# LTC6812-1.net
KiCad netlist of a schematic drawn in Altium Designer
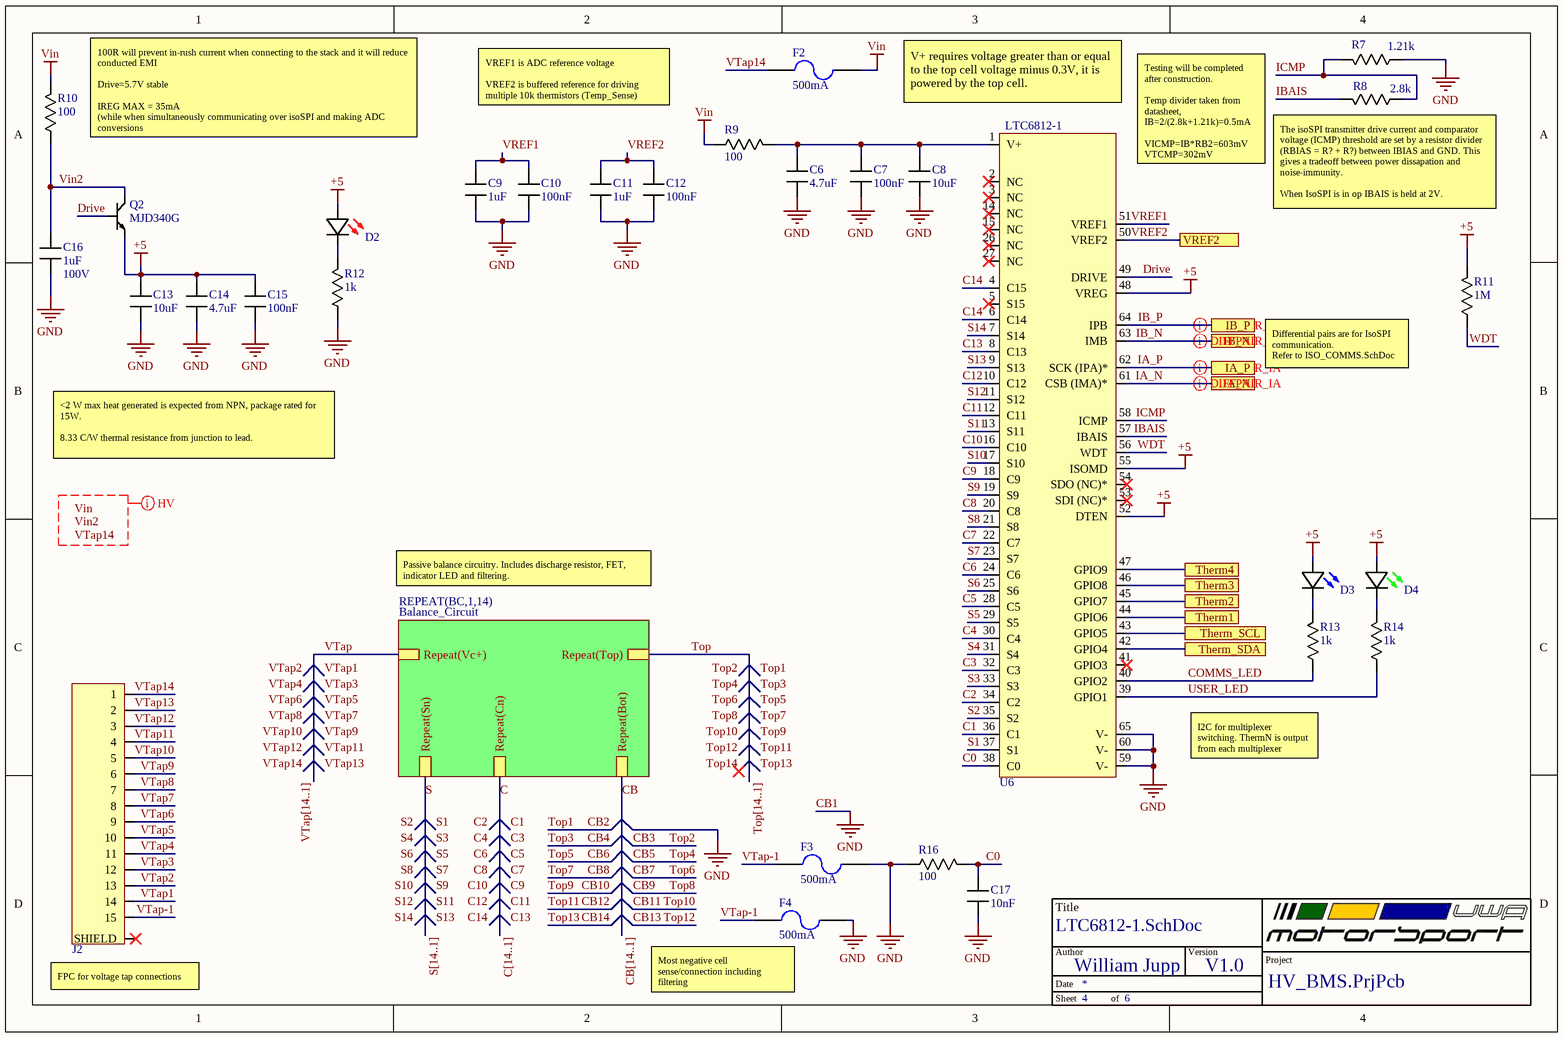
[diagram p0: LTC6812-1.SchDoc]

(export (version "E")
  (design (tool "Eeschema 10.0.6"))
  (components
    (comp (ref "C6")
      (value "4.7uF")
      (footprint "C_0603")
      (description "Capacitor")
      (fields (field (name "Comment") "C"))
      (libsource (lib "Passives") (part "Capacitor"))
    )
    (comp (ref "C7")
      (value "100nF")
      (footprint "C_0603")
      (description "Capacitor")
      (fields (field (name "Comment") "C"))
      (libsource (lib "Passives") (part "Capacitor"))
    )
    (comp (ref "C8")
      (value "10uF")
      (footprint "C_0603")
      (description "Capacitor")
      (fields (field (name "Comment") "C"))
      (libsource (lib "Passives") (part "Capacitor"))
    )
    (comp (ref "C9")
      (value "1uF")
      (footprint "C_0603")
      (description "Bypass caps")
      (fields (field (name "Comment") "C"))
      (libsource (lib "Passives") (part "Capacitor"))
    )
    (comp (ref "C10")
      (value "100nF")
      (footprint "C_0603")
      (description "Bypass caps")
      (fields (field (name "Comment") "C"))
      (libsource (lib "Passives") (part "Capacitor"))
    )
    (comp (ref "C11")
      (value "1uF")
      (footprint "C_0603")
      (description "Bypass caps")
      (fields (field (name "Comment") "C"))
      (libsource (lib "Passives") (part "Capacitor"))
    )
    (comp (ref "C12")
      (value "100nF")
      (footprint "C_0603")
      (description "Bypass caps")
      (fields (field (name "Comment") "C"))
      (libsource (lib "Passives") (part "Capacitor"))
    )
    (comp (ref "C13")
      (value "10uF")
      (footprint "C_0603")
      (description "Capacitor")
      (fields (field (name "Comment") "C"))
      (libsource (lib "Passives") (part "Capacitor"))
    )
    (comp (ref "C14")
      (value "4.7uF")
      (footprint "C_0603")
      (description "Capacitor")
      (fields (field (name "Comment") "C"))
      (libsource (lib "Passives") (part "Capacitor"))
    )
    (comp (ref "C15")
      (value "100nF")
      (footprint "C_0603")
      (description "Capacitor")
      (fields (field (name "Comment") "C"))
      (libsource (lib "Passives") (part "Capacitor"))
    )
    (comp (ref "C16")
      (value "1uF")
      (footprint "C_0603")
      (description "Capacitor")
      (fields (field (name "VOLTAGE") "100V") (field (name "Comment") "C"))
      (libsource (lib "Passives") (part "Capacitor"))
    )
    (comp (ref "C17")
      (value "10nF")
      (footprint "C_0603")
      (description "Capacitor")
      (fields (field (name "Comment") "C"))
      (libsource (lib "Passives") (part "Capacitor"))
    )
    (comp (ref "D2")
      (value "150060SS55040")
      (footprint "LED (0603)")
      (description "LED RED DIFFUSED 0603 SMD")
      (fields (field (name "MANUFACTURER") "Wurth Electronics"))
      (libsource (lib "LEDLib") (part "150060SS55040"))
    )
    (comp (ref "D3")
      (value "150060BS55040")
      (footprint "LED (0603)")
      (description "LED BLUE DIFFUSED 0603 SMD")
      (fields (field (name "MANUFACTURER") "Wurth Electronics"))
      (libsource (lib "LEDLib") (part "150060BS55040"))
    )
    (comp (ref "D4")
      (value "150060GS55040")
      (footprint "LED (0603)")
      (description "LED GREEN DIFFUSED 0603 SMD")
      (fields (field (name "MANUFACTURER") "Wurth Electronics"))
      (libsource (lib "LEDLib") (part "150060GS55040"))
    )
    (comp (ref "F2")
      (value "0466.500NR")
      (footprint "0466.500NR")
      (fields
        (field (name "MANUFACTURER") "Littelfuse")
        (field (name "CURRENT RATING") "500mA")
        (field (name "PUBLISHER") "Altium Limited")
      )
      (libsource (lib "Miscellaneous Devices") (part "Fuse 2"))
    )
    (comp (ref "F3")
      (value "0466.500NR")
      (footprint "0466.500NR")
      (fields
        (field (name "MANUFACTURER") "Littelfuse")
        (field (name "CURRENT RATING") "500mA")
        (field (name "PUBLISHER") "Altium Limited")
      )
      (libsource (lib "Miscellaneous Devices") (part "Fuse 2"))
    )
    (comp (ref "F4")
      (value "0466.500NR")
      (footprint "0466.500NR")
      (fields
        (field (name "MANUFACTURER") "Littelfuse")
        (field (name "CURRENT RATING") "500mA")
        (field (name "PUBLISHER") "Altium Limited")
      )
      (libsource (lib "Miscellaneous Devices") (part "Fuse 2"))
    )
    (comp (ref "J2")
      (value "1-84953-5")
      (footprint "1-84953-5")
      (description "Conn FPC Connector SKT 15 POS 1mm Solder RA SMD T/R")
      (fields (field (name "MANUFACTURER") "TE Connectivity"))
      (libsource (lib "TE_Con") (part "1-84953-5"))
    )
    (comp (ref "Q2")
      (value "MJD340G")
      (footprint "TO-252-3")
      (fields (field (name "MANUFACTURER") "ON Semiconductor"))
      (libsource (lib "NPN") (part "MJD340G"))
    )
    (comp (ref "R7")
      (value "1.21k")
      (footprint "R-0603")
      (description "RB2")
      (fields (field (name "Comment") "Resistor"))
      (libsource (lib "Passives") (part "Resistor"))
    )
    (comp (ref "R8")
      (value "2.8k")
      (footprint "R-0603")
      (description "Resistor")
      (fields (field (name "Comment") "RB1"))
      (libsource (lib "") (part "Resistor_1"))
    )
    (comp (ref "R9")
      (value "100")
      (footprint "R_2010")
      (description "Resistor")
      (fields (field (name "Comment") "ERJ-12ZYJ101U"))
      (libsource (lib "Passives") (part "Resistor"))
    )
    (comp (ref "R10")
      (value "100")
      (footprint "R_2010")
      (description "Resistor")
      (fields (field (name "Comment") "ERJ-12ZYJ101U"))
      (libsource (lib "Passives") (part "Resistor"))
    )
    (comp (ref "R11")
      (value "1M")
      (footprint "R-0603")
      (description "Resistor")
      (libsource (lib "Passives") (part "Resistor"))
    )
    (comp (ref "R12")
      (value "1k")
      (footprint "R-0603")
      (description "Resistor")
      (libsource (lib "Passives") (part "Resistor"))
    )
    (comp (ref "R13")
      (value "1k")
      (footprint "R-0603")
      (description "Resistor")
      (libsource (lib "Passives") (part "Resistor"))
    )
    (comp (ref "R14")
      (value "1k")
      (footprint "R-0603")
      (description "Resistor")
      (libsource (lib "Passives") (part "Resistor"))
    )
    (comp (ref "R16")
      (value "100")
      (footprint "R-0603")
      (description "Resistor")
      (libsource (lib "Passives") (part "Resistor"))
    )
    (comp (ref "U6")
      (value "LTC6812-1")
      (footprint "64-eLQFP")
      (description "Multicell battery stack monitor that measures up to 15 series connected battery cells")
      (libsource (lib "HV_BMS_SCH_LIB") (part "LTC6812-1"))
    )
  )
  (nets
    (net (code "1") (name "+5") (class "Default")
      (node (ref "C13") (pin "2") (pinfunction "2_2") (pintype "passive"))
      (node (ref "C14") (pin "2") (pinfunction "2_2") (pintype "passive"))
      (node (ref "C15") (pin "2") (pinfunction "2_2") (pintype "passive"))
      (node (ref "D2") (pin "2") (pinfunction "A_2") (pintype "passive"))
      (node (ref "D3") (pin "2") (pinfunction "A_2") (pintype "passive"))
      (node (ref "D4") (pin "2") (pinfunction "A_2") (pintype "passive"))
      (node (ref "Q2") (pin "3") (pinfunction "Emitter_3") (pintype "passive"))
      (node (ref "R11") (pin "1") (pinfunction "1_1") (pintype "passive"))
      (node (ref "U6") (pin "48") (pinfunction "VREG_48") (pintype "passive"))
      (node (ref "U6") (pin "52") (pinfunction "DTEN_52") (pintype "passive"))
      (node (ref "U6") (pin "55") (pinfunction "ISOMD_55") (pintype "passive"))
    )
    (net (code "3") (name "/C0") (class "Default")
      (node (ref "C17") (pin "2") (pinfunction "2_2") (pintype "passive"))
      (node (ref "R16") (pin "2") (pinfunction "2_2") (pintype "passive"))
      (node (ref "U6") (pin "38") (pinfunction "C0_38") (pintype "passive"))
    )
    (net (code "4") (name "/C1") (class "Default")
      (node (ref "U6") (pin "36") (pinfunction "C1_36") (pintype "passive"))
    )
    (net (code "5") (name "/C2") (class "Default")
      (node (ref "U6") (pin "34") (pinfunction "C2_34") (pintype "passive"))
    )
    (net (code "6") (name "/C3") (class "Default")
      (node (ref "U6") (pin "32") (pinfunction "C3_32") (pintype "passive"))
    )
    (net (code "7") (name "/C4") (class "Default")
      (node (ref "U6") (pin "30") (pinfunction "C4_30") (pintype "passive"))
    )
    (net (code "8") (name "/C5") (class "Default")
      (node (ref "U6") (pin "28") (pinfunction "C5_28") (pintype "passive"))
    )
    (net (code "9") (name "/C6") (class "Default")
      (node (ref "U6") (pin "24") (pinfunction "C6_24") (pintype "passive"))
    )
    (net (code "10") (name "/C7") (class "Default")
      (node (ref "U6") (pin "22") (pinfunction "C7_22") (pintype "passive"))
    )
    (net (code "11") (name "/C8") (class "Default")
      (node (ref "U6") (pin "20") (pinfunction "C8_20") (pintype "passive"))
    )
    (net (code "12") (name "/C9") (class "Default")
      (node (ref "U6") (pin "18") (pinfunction "C9_18") (pintype "passive"))
    )
    (net (code "13") (name "/C10") (class "Default")
      (node (ref "U6") (pin "16") (pinfunction "C10_16") (pintype "passive"))
    )
    (net (code "14") (name "/C11") (class "Default")
      (node (ref "U6") (pin "12") (pinfunction "C11_12") (pintype "passive"))
    )
    (net (code "15") (name "/C12") (class "Default")
      (node (ref "U6") (pin "10") (pinfunction "C12_10") (pintype "passive"))
    )
    (net (code "16") (name "/C13") (class "Default")
      (node (ref "U6") (pin "8") (pinfunction "C13_8") (pintype "passive"))
    )
    (net (code "17") (name "/C14") (class "Default")
      (node (ref "U6") (pin "4") (pinfunction "C15_4") (pintype "passive"))
      (node (ref "U6") (pin "6") (pinfunction "C14_6") (pintype "passive"))
    )
    (net (code "20") (name "/COMMS_LED") (class "Default")
      (node (ref "R13") (pin "1") (pinfunction "1_1") (pintype "passive"))
      (node (ref "U6") (pin "40") (pinfunction "GPIO2_40") (pintype "passive"))
    )
    (net (code "22") (name "/Drive") (class "Default")
      (node (ref "Q2") (pin "1") (pinfunction "Base_1") (pintype "passive"))
      (node (ref "U6") (pin "49") (pinfunction "DRIVE_49") (pintype "passive"))
    )
    (net (code "23") (name "/IA_N") (class "Default")
      (node (ref "U6") (pin "61") (pinfunction "CSB_(IMA)*_61") (pintype "passive"))
    )
    (net (code "24") (name "/IA_P") (class "Default")
      (node (ref "U6") (pin "62") (pinfunction "SCK_(IPA)*_62") (pintype "passive"))
    )
    (net (code "25") (name "/IBAIS") (class "Default")
      (node (ref "R8") (pin "2") (pinfunction "2_2") (pintype "passive"))
      (node (ref "U6") (pin "57") (pinfunction "IBAIS_57") (pintype "passive"))
    )
    (net (code "26") (name "/IB_N") (class "Default")
      (node (ref "U6") (pin "63") (pinfunction "IMB_63") (pintype "passive"))
    )
    (net (code "27") (name "/IB_P") (class "Default")
      (node (ref "U6") (pin "64") (pinfunction "IPB_64") (pintype "passive"))
    )
    (net (code "28") (name "/ICMP") (class "Default")
      (node (ref "R7") (pin "2") (pinfunction "2_2") (pintype "passive"))
      (node (ref "R8") (pin "1") (pinfunction "1_1") (pintype "passive"))
      (node (ref "U6") (pin "58") (pinfunction "ICMP_58") (pintype "passive"))
    )
    (net (code "30") (name "/S1") (class "Default")
      (node (ref "U6") (pin "37") (pinfunction "S1_37") (pintype "passive"))
    )
    (net (code "31") (name "/S2") (class "Default")
      (node (ref "U6") (pin "35") (pinfunction "S2_35") (pintype "passive"))
    )
    (net (code "32") (name "/S3") (class "Default")
      (node (ref "U6") (pin "33") (pinfunction "S3_33") (pintype "passive"))
    )
    (net (code "33") (name "/S4") (class "Default")
      (node (ref "U6") (pin "31") (pinfunction "S4_31") (pintype "passive"))
    )
    (net (code "34") (name "/S5") (class "Default")
      (node (ref "U6") (pin "29") (pinfunction "S5_29") (pintype "passive"))
    )
    (net (code "35") (name "/S6") (class "Default")
      (node (ref "U6") (pin "25") (pinfunction "S6_25") (pintype "passive"))
    )
    (net (code "36") (name "/S7") (class "Default")
      (node (ref "U6") (pin "23") (pinfunction "S7_23") (pintype "passive"))
    )
    (net (code "37") (name "/S8") (class "Default")
      (node (ref "U6") (pin "21") (pinfunction "S8_21") (pintype "passive"))
    )
    (net (code "38") (name "/S9") (class "Default")
      (node (ref "U6") (pin "19") (pinfunction "S9_19") (pintype "passive"))
    )
    (net (code "39") (name "/S10") (class "Default")
      (node (ref "U6") (pin "17") (pinfunction "S10_17") (pintype "passive"))
    )
    (net (code "40") (name "/S11") (class "Default")
      (node (ref "U6") (pin "13") (pinfunction "S11_13") (pintype "passive"))
    )
    (net (code "41") (name "/S12") (class "Default")
      (node (ref "U6") (pin "11") (pinfunction "S12_11") (pintype "passive"))
    )
    (net (code "42") (name "/S13") (class "Default")
      (node (ref "U6") (pin "9") (pinfunction "S13_9") (pintype "passive"))
    )
    (net (code "43") (name "/S14") (class "Default")
      (node (ref "U6") (pin "7") (pinfunction "S14_7") (pintype "passive"))
    )
    (net (code "45") (name "/Therm1") (class "Default")
      (node (ref "U6") (pin "44") (pinfunction "GPIO6_44") (pintype "passive"))
    )
    (net (code "46") (name "/Therm2") (class "Default")
      (node (ref "U6") (pin "45") (pinfunction "GPIO7_45") (pintype "passive"))
    )
    (net (code "47") (name "/Therm3") (class "Default")
      (node (ref "U6") (pin "46") (pinfunction "GPIO8_46") (pintype "passive"))
    )
    (net (code "48") (name "/Therm4") (class "Default")
      (node (ref "U6") (pin "47") (pinfunction "GPIO9_47") (pintype "passive"))
    )
    (net (code "49") (name "/Therm_SCL") (class "Default")
      (node (ref "U6") (pin "43") (pinfunction "GPIO5_43") (pintype "passive"))
    )
    (net (code "50") (name "/Therm_SDA") (class "Default")
      (node (ref "U6") (pin "42") (pinfunction "GPIO4_42") (pintype "passive"))
    )
    (net (code "67") (name "/USER_LED") (class "Default")
      (node (ref "R14") (pin "1") (pinfunction "1_1") (pintype "passive"))
      (node (ref "U6") (pin "39") (pinfunction "GPIO1_39") (pintype "passive"))
    )
    (net (code "68") (name "/VREF1") (class "Default")
      (node (ref "C10") (pin "2") (pinfunction "2_2") (pintype "passive"))
      (node (ref "C9") (pin "2") (pinfunction "2_2") (pintype "passive"))
      (node (ref "U6") (pin "51") (pinfunction "VREF1_51") (pintype "passive"))
    )
    (net (code "69") (name "/VREF2") (class "Default")
      (node (ref "C11") (pin "2") (pinfunction "2_2") (pintype "passive"))
      (node (ref "C12") (pin "2") (pinfunction "2_2") (pintype "passive"))
      (node (ref "U6") (pin "50") (pinfunction "VREF2_50") (pintype "passive"))
    )
    (net (code "71") (name "/VTap-1") (class "Default")
      (node (ref "F3") (pin "1") (pinfunction "1_1") (pintype "passive"))
      (node (ref "F4") (pin "1") (pinfunction "1_1") (pintype "passive"))
      (node (ref "J2") (pin "15") (pinfunction "15_15") (pintype "passive"))
    )
    (net (code "72") (name "/VTap1") (class "Default")
      (node (ref "J2") (pin "14") (pinfunction "14_14") (pintype "passive"))
    )
    (net (code "73") (name "/VTap2") (class "Default")
      (node (ref "J2") (pin "13") (pinfunction "13_13") (pintype "passive"))
    )
    (net (code "74") (name "/VTap3") (class "Default")
      (node (ref "J2") (pin "12") (pinfunction "12_12") (pintype "passive"))
    )
    (net (code "75") (name "/VTap4") (class "Default")
      (node (ref "J2") (pin "11") (pinfunction "11_11") (pintype "passive"))
    )
    (net (code "76") (name "/VTap5") (class "Default")
      (node (ref "J2") (pin "10") (pinfunction "10_10") (pintype "passive"))
    )
    (net (code "77") (name "/VTap6") (class "Default")
      (node (ref "J2") (pin "9") (pinfunction "9_9") (pintype "passive"))
    )
    (net (code "78") (name "/VTap7") (class "Default")
      (node (ref "J2") (pin "8") (pinfunction "8_8") (pintype "passive"))
    )
    (net (code "79") (name "/VTap8") (class "Default")
      (node (ref "J2") (pin "7") (pinfunction "7_7") (pintype "passive"))
    )
    (net (code "80") (name "/VTap9") (class "Default")
      (node (ref "J2") (pin "6") (pinfunction "6_6") (pintype "passive"))
    )
    (net (code "81") (name "/VTap10") (class "Default")
      (node (ref "J2") (pin "5") (pinfunction "5_5") (pintype "passive"))
    )
    (net (code "82") (name "/VTap11") (class "Default")
      (node (ref "J2") (pin "4") (pinfunction "4_4") (pintype "passive"))
    )
    (net (code "83") (name "/VTap12") (class "Default")
      (node (ref "J2") (pin "3") (pinfunction "3_3") (pintype "passive"))
    )
    (net (code "84") (name "/VTap13") (class "Default")
      (node (ref "J2") (pin "2") (pinfunction "2_2") (pintype "passive"))
    )
    (net (code "85") (name "/VTap14") (class "Default")
      (node (ref "F2") (pin "1") (pinfunction "1_1") (pintype "passive"))
      (node (ref "J2") (pin "1") (pinfunction "1_1") (pintype "passive"))
    )
    (net (code "87") (name "/Vin2") (class "Default")
      (node (ref "C16") (pin "2") (pinfunction "2_2") (pintype "passive"))
      (node (ref "Q2") (pin "2") (pinfunction "Collector_2") (pintype "passive"))
      (node (ref "R10") (pin "1") (pinfunction "1_1") (pintype "passive"))
    )
    (net (code "88") (name "/WDT") (class "Default")
      (node (ref "R11") (pin "2") (pinfunction "2_2") (pintype "passive"))
      (node (ref "U6") (pin "56") (pinfunction "WDT_56") (pintype "passive"))
    )
    (net (code "89") (name "GND") (class "Default")
      (node (ref "C10") (pin "1") (pinfunction "1_1") (pintype "passive"))
      (node (ref "C11") (pin "1") (pinfunction "1_1") (pintype "passive"))
      (node (ref "C12") (pin "1") (pinfunction "1_1") (pintype "passive"))
      (node (ref "C13") (pin "1") (pinfunction "1_1") (pintype "passive"))
      (node (ref "C14") (pin "1") (pinfunction "1_1") (pintype "passive"))
      (node (ref "C15") (pin "1") (pinfunction "1_1") (pintype "passive"))
      (node (ref "C16") (pin "1") (pinfunction "1_1") (pintype "passive"))
      (node (ref "C17") (pin "1") (pinfunction "1_1") (pintype "passive"))
      (node (ref "C6") (pin "1") (pinfunction "1_1") (pintype "passive"))
      (node (ref "C7") (pin "1") (pinfunction "1_1") (pintype "passive"))
      (node (ref "C8") (pin "1") (pinfunction "1_1") (pintype "passive"))
      (node (ref "C9") (pin "1") (pinfunction "1_1") (pintype "passive"))
      (node (ref "F3") (pin "2") (pinfunction "2_2") (pintype "passive"))
      (node (ref "F4") (pin "2") (pinfunction "2_2") (pintype "passive"))
      (node (ref "R12") (pin "1") (pinfunction "1_1") (pintype "passive"))
      (node (ref "R16") (pin "1") (pinfunction "1_1") (pintype "passive"))
      (node (ref "R7") (pin "1") (pinfunction "1_1") (pintype "passive"))
      (node (ref "U6") (pin "59") (pinfunction "V-_59") (pintype "passive"))
      (node (ref "U6") (pin "60") (pinfunction "V-_60") (pintype "passive"))
      (node (ref "U6") (pin "65") (pinfunction "V-_65") (pintype "passive"))
    )
    (net (code "90") (name "Net-(D2-K)") (class "Default")
      (node (ref "D2") (pin "1") (pinfunction "K_1") (pintype "passive"))
      (node (ref "R12") (pin "2") (pinfunction "2_2") (pintype "passive"))
    )
    (net (code "91") (name "Net-(D3-K)") (class "Default")
      (node (ref "D3") (pin "1") (pinfunction "K_1") (pintype "passive"))
      (node (ref "R13") (pin "2") (pinfunction "2_2") (pintype "passive"))
    )
    (net (code "92") (name "Net-(D4-K)") (class "Default")
      (node (ref "D4") (pin "1") (pinfunction "K_1") (pintype "passive"))
      (node (ref "R14") (pin "2") (pinfunction "2_2") (pintype "passive"))
    )
    (net (code "93") (name "Net-(U6-V+)") (class "Default")
      (node (ref "C6") (pin "2") (pinfunction "2_2") (pintype "passive"))
      (node (ref "C7") (pin "2") (pinfunction "2_2") (pintype "passive"))
      (node (ref "C8") (pin "2") (pinfunction "2_2") (pintype "passive"))
      (node (ref "R9") (pin "2") (pinfunction "2_2") (pintype "passive"))
      (node (ref "U6") (pin "1") (pinfunction "V+_1") (pintype "passive"))
    )
    (net (code "94") (name "Vin") (class "Default")
      (node (ref "F2") (pin "2") (pinfunction "2_2") (pintype "passive"))
      (node (ref "R10") (pin "2") (pinfunction "2_2") (pintype "passive"))
      (node (ref "R9") (pin "1") (pinfunction "1_1") (pintype "passive"))
    )
    (net (code "95") (name "unconnected-(J2-SHIELD-PadS)") (class "Default")
      (node (ref "J2") (pin "S") (pinfunction "SHIELD_S") (pintype "passive+no_connect"))
    )
    (net (code "96") (name "unconnected-(U6-GPIO3-Pad41)") (class "Default")
      (node (ref "U6") (pin "41") (pinfunction "GPIO3_41") (pintype "passive+no_connect"))
    )
    (net (code "97") (name "unconnected-(U6-NC-Pad2)") (class "Default")
      (node (ref "U6") (pin "2") (pinfunction "NC_2") (pintype "passive+no_connect"))
    )
    (net (code "98") (name "unconnected-(U6-NC-Pad3)") (class "Default")
      (node (ref "U6") (pin "3") (pinfunction "NC_3") (pintype "passive+no_connect"))
    )
    (net (code "99") (name "unconnected-(U6-NC-Pad14)") (class "Default")
      (node (ref "U6") (pin "14") (pinfunction "NC_14") (pintype "passive+no_connect"))
    )
    (net (code "100") (name "unconnected-(U6-NC-Pad15)") (class "Default")
      (node (ref "U6") (pin "15") (pinfunction "NC_15") (pintype "passive+no_connect"))
    )
    (net (code "101") (name "unconnected-(U6-NC-Pad26)") (class "Default")
      (node (ref "U6") (pin "26") (pinfunction "NC_26") (pintype "passive+no_connect"))
    )
    (net (code "102") (name "unconnected-(U6-NC-Pad27)") (class "Default")
      (node (ref "U6") (pin "27") (pinfunction "NC_27") (pintype "passive+no_connect"))
    )
    (net (code "103") (name "unconnected-(U6-S15-Pad5)") (class "Default")
      (node (ref "U6") (pin "5") (pinfunction "S15_5") (pintype "passive+no_connect"))
    )
    (net (code "104") (name "unconnected-(U6-SDI_(NC)*-Pad53)") (class "Default")
      (node (ref "U6") (pin "53") (pinfunction "SDI_(NC)*_53") (pintype "passive+no_connect"))
    )
    (net (code "105") (name "unconnected-(U6-SDO_(NC)*-Pad54)") (class "Default")
      (node (ref "U6") (pin "54") (pinfunction "SDO_(NC)*_54") (pintype "passive+no_connect"))
    )
  )
)
